# MCU.net
KiCad netlist of a schematic drawn in Altium Designer
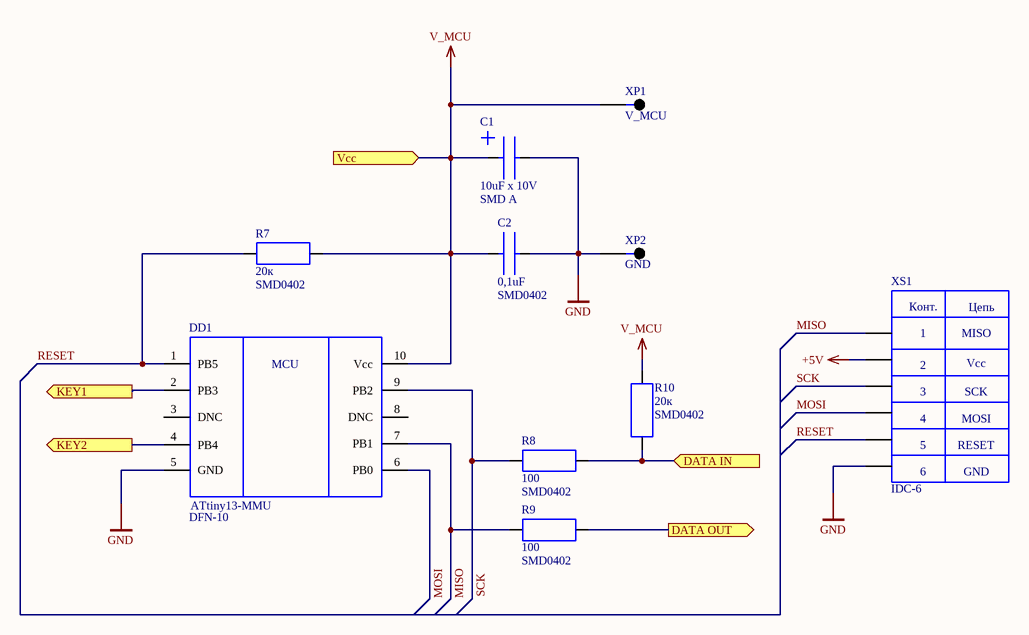
[diagram p0: MCU.SchDoc]

(export (version "E")
  (design (tool "Eeschema 10.0.6"))
  (components
    (comp (ref "C1")
      (value "10uF x 10V")
      (footprint "TANT_CAP_A(3216)")
      (fields (field (name "PACKAGE") "SMD A"))
      (libsource (lib "MechanikLibrary") (part "C_TANT_A"))
    )
    (comp (ref "C2")
      (value "0,1uF")
      (footprint "SMD0402(1608)")
      (fields (field (name "PACKAGE") "SMD0402"))
      (libsource (lib "MechanikLibrary") (part "CER_CUP_0402"))
    )
    (comp (ref "DD1")
      (value "ATtiny13-MMU")
      (footprint "QFN-10")
      (fields (field (name "PACKAGE") "DFN-10"))
      (libsource (lib "MechanikLibrary") (part "ATtiny13-MMU"))
    )
    (comp (ref "R7")
      (value "20к")
      (footprint "SMD0402(1608)")
      (fields (field (name "PACKAGE") "SMD0402"))
      (libsource (lib "MechanikLibrary") (part "R_0402"))
    )
    (comp (ref "R8")
      (value "100")
      (footprint "SMD0402(1608)")
      (fields (field (name "PACKAGE") "SMD0402"))
      (libsource (lib "MechanikLibrary") (part "R_0402"))
    )
    (comp (ref "R9")
      (value "100")
      (footprint "SMD0402(1608)")
      (fields (field (name "PACKAGE") "SMD0402"))
      (libsource (lib "MechanikLibrary") (part "R_0402"))
    )
    (comp (ref "R10")
      (value "20к")
      (footprint "SMD0402(1608)")
      (fields (field (name "PACKAGE") "SMD0402"))
      (libsource (lib "MechanikLibrary") (part "R_0402"))
    )
    (comp (ref "XP1")
      (value "V_MCU")
      (footprint "XP_solder")
      (libsource (lib "MechanikLibrary") (part "XP_solder"))
    )
    (comp (ref "XP2")
      (value "GND")
      (footprint "XP_solder")
      (libsource (lib "MechanikLibrary") (part "XP_solder"))
    )
    (comp (ref "XS1")
      (value "IDC-6")
      (footprint "IDC-6 (2.54)")
      (libsource (lib "MechanikLibrary") (part "ISP_connector"))
    )
  )
  (nets
    (net (code "1") (name "+5V") (class "Default")
      (node (ref "XS1") (pin "2") (pinfunction "DM-_2") (pintype "passive"))
    )
    (net (code "2") (name "/DATA IN") (class "Default")
      (node (ref "R10") (pin "2") (pintype "passive"))
      (node (ref "R8") (pin "1") (pintype "passive"))
    )
    (net (code "3") (name "/DATA OUT") (class "Default") (node (ref "R9") (pin "1") (pintype "passive")))
    (net (code "4") (name "/KEY1") (class "Default")
      (node (ref "DD1") (pin "2") (pinfunction "PB3_2") (pintype "passive"))
    )
    (net (code "5") (name "/KEY2") (class "Default")
      (node (ref "DD1") (pin "4") (pinfunction "PB4_4") (pintype "passive"))
    )
    (net (code "6") (name "/MISO") (class "Default")
      (node (ref "DD1") (pin "7") (pinfunction "PB1_7") (pintype "passive"))
      (node (ref "R9") (pin "2") (pintype "passive"))
      (node (ref "XS1") (pin "1") (pinfunction "+5_1") (pintype "passive"))
    )
    (net (code "7") (name "/MOSI") (class "Default")
      (node (ref "DD1") (pin "6") (pinfunction "PB0_6") (pintype "passive"))
      (node (ref "XS1") (pin "4") (pinfunction "DM+_4") (pintype "passive"))
    )
    (net (code "8") (name "/RESET") (class "Default")
      (node (ref "DD1") (pin "1") (pinfunction "PB5_1") (pintype "passive"))
      (node (ref "R7") (pin "2") (pintype "passive"))
      (node (ref "XS1") (pin "5") (pinfunction "DM+_5") (pintype "passive"))
    )
    (net (code "9") (name "/SCK") (class "Default")
      (node (ref "DD1") (pin "9") (pinfunction "PB2_9") (pintype "passive"))
      (node (ref "R8") (pin "2") (pintype "passive"))
      (node (ref "XS1") (pin "3") (pinfunction "DM+_3") (pintype "passive"))
    )
    (net (code "10") (name "GND") (class "Default")
      (node (ref "C1") (pin "2") (pintype "passive"))
      (node (ref "C2") (pin "2") (pintype "passive"))
      (node (ref "DD1") (pin "5") (pinfunction "GND_5") (pintype "passive"))
      (node (ref "XP2") (pin "1") (pinfunction "1_1") (pintype "passive"))
      (node (ref "XS1") (pin "6") (pinfunction "DM+_6") (pintype "passive"))
    )
    (net (code "11") (name "V_MCU") (class "Default")
      (node (ref "C1") (pin "1") (pintype "passive"))
      (node (ref "C2") (pin "1") (pintype "passive"))
      (node (ref "DD1") (pin "10") (pinfunction "Vcc_10") (pintype "passive"))
      (node (ref "R10") (pin "1") (pintype "passive"))
      (node (ref "R7") (pin "1") (pintype "passive"))
      (node (ref "XP1") (pin "1") (pinfunction "1_1") (pintype "passive"))
    )
    (net (code "12") (name "unconnected-(DD1-DNC-Pad3)") (class "Default")
      (node (ref "DD1") (pin "3") (pinfunction "DNC_3") (pintype "passive"))
    )
    (net (code "13") (name "unconnected-(DD1-DNC-Pad8)") (class "Default")
      (node (ref "DD1") (pin "8") (pinfunction "DNC_8") (pintype "passive"))
    )
  )
)
